# Sensor.net
KiCad netlist of a schematic drawn in Altium Designer
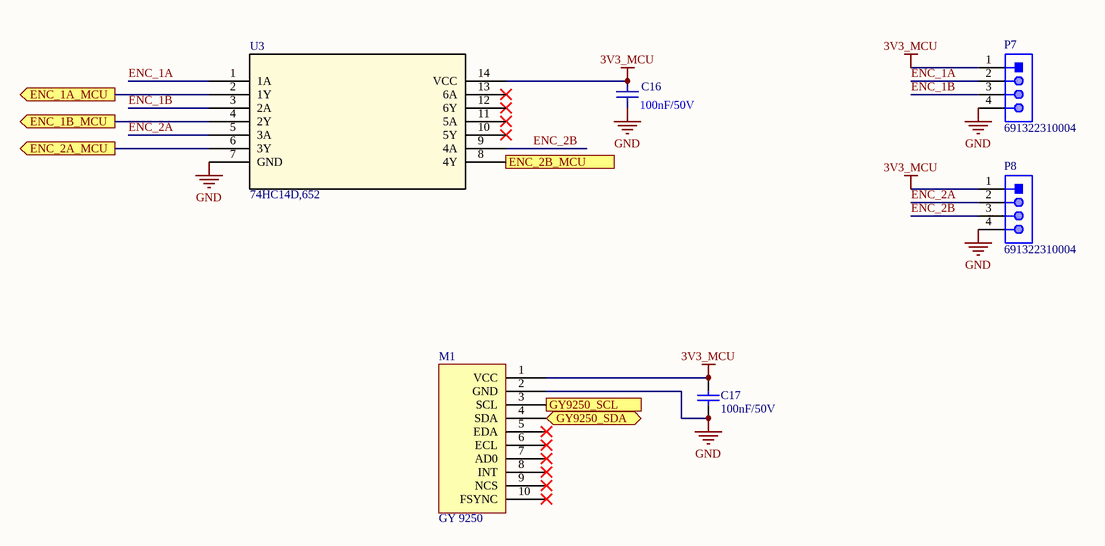
[diagram p0: Sensor.SchDoc]

(export (version "E")
  (design (tool "Eeschema 10.0.6"))
  (components
    (comp (ref "C16")
      (value "100nF/50V")
      (footprint "CAP-SM-0805")
      (description "Capacitor")
      (fields (field (name "Comment") "Cap Non-Pol SMD"))
      (libsource (lib "PIF_C16_lib") (part "Cap Non-Pol SMD"))
    )
    (comp (ref "C17")
      (value "100nF/50V")
      (footprint "CAP-SM-0805")
      (description "CAP CER 1000PF 100V X7R 0805")
      (fields
        (field (name "MANUFACTURER") "Johanson Dielectrics Inc.")
        (field (name "MANUFACTURER PART NUMBER") "101X15W102MV4E")
      )
      (libsource (lib "Capacitor") (part "Cap-1nF-50V-0805"))
    )
    (comp (ref "M1") (value "GY 9250") (footprint "GY 9250") (libsource (lib "Schlib1") (part "GY 9250")))
    (comp (ref "P7")
      (value "691322310004")
      (footprint "691322310004")
      (description "WR-TBL Serie 322 Horizontal PCB Header, Pluggable, pitch 3.81mm, 4p")
      (fields (field (name "PUBLISHER") "Wurth Elektronik"))
      (libsource (lib "691101710002_Altium_WR-TBL_rev19a") (part "691322310004"))
    )
    (comp (ref "P8")
      (value "691322310004")
      (footprint "691322310004")
      (description "WR-TBL Serie 322 Horizontal PCB Header, Pluggable, pitch 3.81mm, 4p")
      (fields (field (name "PUBLISHER") "Wurth Elektronik"))
      (libsource (lib "691101710002_Altium_WR-TBL_rev19a") (part "691322310004"))
    )
    (comp (ref "U3")
      (value "74HC14D,652")
      (footprint "74HC14D,652")
      (fields (field (name "COPYRIGHT") "Copyright (C) 2016 Accelerated Designs. All rights reserved"))
      (libsource (lib "Integrated_Library") (part "74HC14D,652"))
    )
  )
  (nets
    (net (code "1") (name "/ENC_1A") (class "Default")
      (node (ref "P7") (pin "2") (pinfunction "2_2") (pintype "passive"))
      (node (ref "U3") (pin "1") (pinfunction "1A_1") (pintype "open_collector"))
    )
    (net (code "2") (name "/ENC_1A_MCU") (class "Default")
      (node (ref "U3") (pin "2") (pinfunction "1Y_2") (pintype "open_collector"))
    )
    (net (code "3") (name "/ENC_1B") (class "Default")
      (node (ref "P7") (pin "3") (pinfunction "3_3") (pintype "passive"))
      (node (ref "U3") (pin "3") (pinfunction "2A_3") (pintype "open_collector"))
    )
    (net (code "4") (name "/ENC_1B_MCU") (class "Default")
      (node (ref "U3") (pin "4") (pinfunction "2Y_4") (pintype "open_collector"))
    )
    (net (code "5") (name "/ENC_2A") (class "Default")
      (node (ref "P8") (pin "2") (pinfunction "2_2") (pintype "passive"))
      (node (ref "U3") (pin "5") (pinfunction "3A_5") (pintype "open_collector"))
    )
    (net (code "6") (name "/ENC_2A_MCU") (class "Default")
      (node (ref "U3") (pin "6") (pinfunction "3Y_6") (pintype "open_collector"))
    )
    (net (code "7") (name "/ENC_2B") (class "Default")
      (node (ref "P8") (pin "3") (pinfunction "3_3") (pintype "passive"))
      (node (ref "U3") (pin "9") (pinfunction "4A_9") (pintype "open_collector"))
    )
    (net (code "8") (name "/ENC_2B_MCU") (class "Default")
      (node (ref "U3") (pin "8") (pinfunction "4Y_8") (pintype "open_collector"))
    )
    (net (code "9") (name "/GY9250_SCL") (class "Default")
      (node (ref "M1") (pin "3") (pinfunction "SCL_3") (pintype "passive"))
    )
    (net (code "10") (name "/GY9250_SDA") (class "Default")
      (node (ref "M1") (pin "4") (pinfunction "SDA_4") (pintype "passive"))
    )
    (net (code "11") (name "3V3_MCU") (class "Default")
      (node (ref "C16") (pin "2") (pinfunction "2_2") (pintype "passive"))
      (node (ref "C17") (pin "2") (pinfunction "2_2") (pintype "passive"))
      (node (ref "M1") (pin "1") (pinfunction "VCC_1") (pintype "passive"))
      (node (ref "P7") (pin "1") (pinfunction "1_1") (pintype "passive"))
      (node (ref "P8") (pin "1") (pinfunction "1_1") (pintype "passive"))
      (node (ref "U3") (pin "14") (pinfunction "VCC_14") (pintype "open_collector"))
    )
    (net (code "12") (name "GND") (class "Default")
      (node (ref "C16") (pin "1") (pinfunction "1_1") (pintype "passive"))
      (node (ref "C17") (pin "1") (pinfunction "1_1") (pintype "passive"))
      (node (ref "M1") (pin "2") (pinfunction "GND_2") (pintype "passive"))
      (node (ref "P7") (pin "4") (pinfunction "4_4") (pintype "passive"))
      (node (ref "P8") (pin "4") (pinfunction "4_4") (pintype "passive"))
      (node (ref "U3") (pin "7") (pinfunction "GND_7") (pintype "open_collector"))
    )
    (net (code "13") (name "unconnected-(M1-AD0-Pad7)") (class "Default")
      (node (ref "M1") (pin "7") (pinfunction "AD0_7") (pintype "passive+no_connect"))
    )
    (net (code "14") (name "unconnected-(M1-ECL-Pad6)") (class "Default")
      (node (ref "M1") (pin "6") (pinfunction "ECL_6") (pintype "passive+no_connect"))
    )
    (net (code "15") (name "unconnected-(M1-EDA-Pad5)") (class "Default")
      (node (ref "M1") (pin "5") (pinfunction "EDA_5") (pintype "passive+no_connect"))
    )
    (net (code "16") (name "unconnected-(M1-FSYNC-Pad10)") (class "Default")
      (node (ref "M1") (pin "10") (pinfunction "FSYNC_10") (pintype "passive+no_connect"))
    )
    (net (code "17") (name "unconnected-(M1-INT-Pad8)") (class "Default")
      (node (ref "M1") (pin "8") (pinfunction "INT_8") (pintype "passive+no_connect"))
    )
    (net (code "18") (name "unconnected-(M1-NCS-Pad9)") (class "Default")
      (node (ref "M1") (pin "9") (pinfunction "NCS_9") (pintype "passive+no_connect"))
    )
    (net (code "19") (name "unconnected-(U3-5A-Pad11)") (class "Default")
      (node (ref "U3") (pin "11") (pinfunction "5A_11") (pintype "open_collector+no_connect"))
    )
    (net (code "20") (name "unconnected-(U3-5Y-Pad10)") (class "Default")
      (node (ref "U3") (pin "10") (pinfunction "5Y_10") (pintype "open_collector+no_connect"))
    )
    (net (code "21") (name "unconnected-(U3-6A-Pad13)") (class "Default")
      (node (ref "U3") (pin "13") (pinfunction "6A_13") (pintype "open_collector+no_connect"))
    )
    (net (code "22") (name "unconnected-(U3-6Y-Pad12)") (class "Default")
      (node (ref "U3") (pin "12") (pinfunction "6Y_12") (pintype "open_collector+no_connect"))
    )
  )
)
